# Dash22_LEDS.net
KiCad netlist of a schematic drawn in Altium Designer
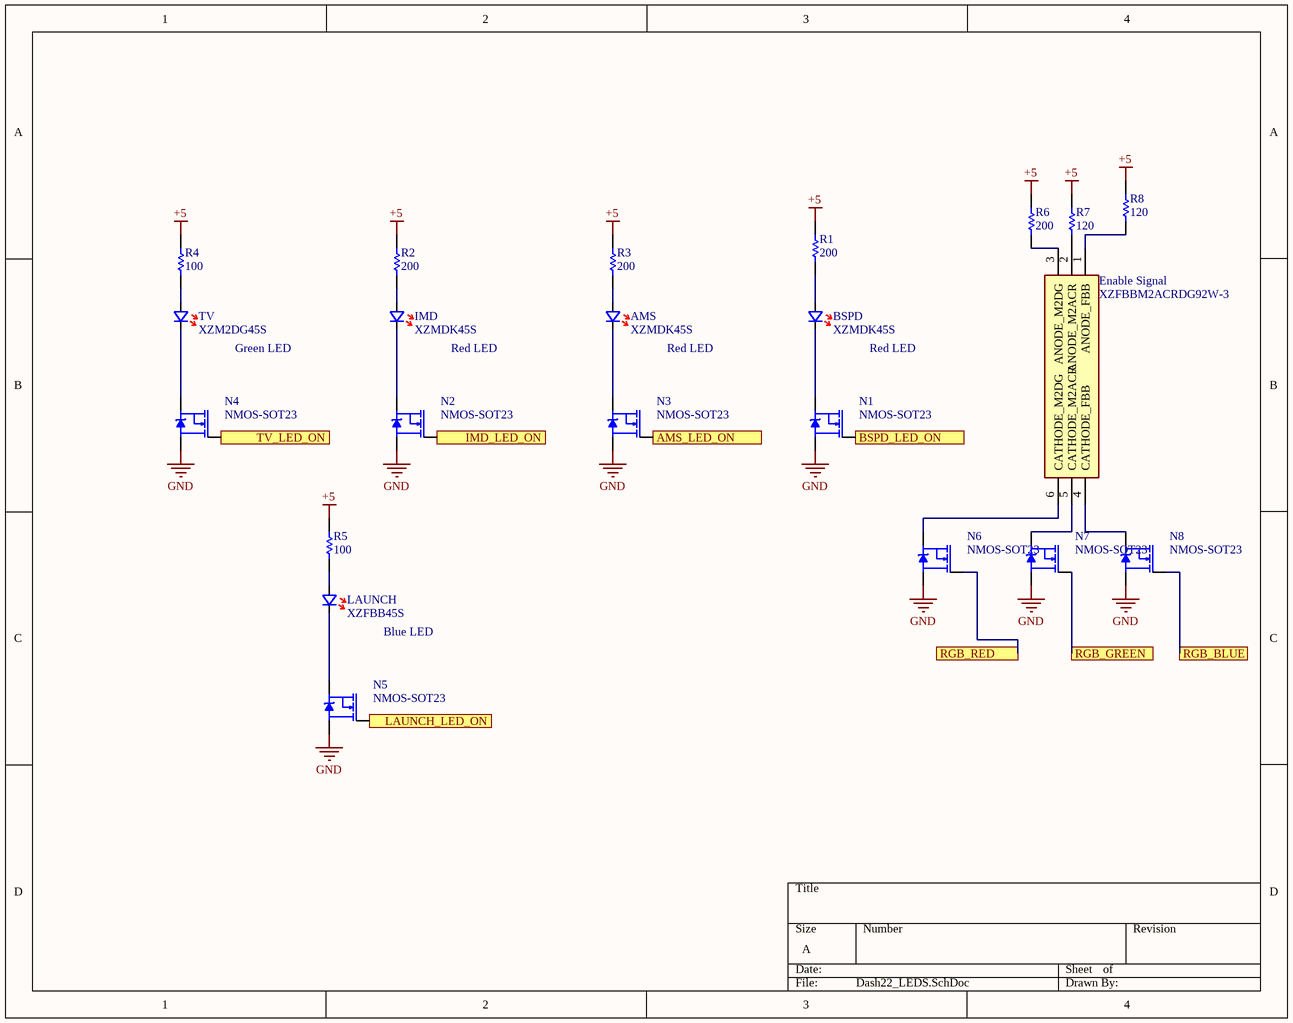
[diagram p0: Dash22_LEDS.SchDoc]

(export (version "E")
  (design (tool "Eeschema 10.0.6"))
  (components
    (comp (ref "AMS")
      (value "XZMDK45S")
      (footprint "LED_XZFBB45S")
      (fields (field (name "SOURCE") "ife19_Elec_Library.schlib"))
      (libsource (lib "") (part "Symbol_1"))
    )
    (comp (ref "BSPD")
      (value "XZMDK45S")
      (footprint "LED_XZFBB45S")
      (fields (field (name "SOURCE") "ife19_Elec_Library.schlib"))
      (libsource (lib "") (part "Symbol_1"))
    )
    (comp (ref "Enable Signal")
      (value "XZFBBM2ACRDG92W-3")
      (footprint "SamacSys:XZFBBM2ACRDG92W3")
      (description "LED")
      (libsource (lib "*") (part "XZFBBM2ACRDG92W-3"))
    )
    (comp (ref "IMD")
      (value "XZMDK45S")
      (footprint "LED_XZFBB45S")
      (fields (field (name "SOURCE") "ife19_Elec_Library.schlib"))
      (libsource (lib "") (part "Symbol_1"))
    )
    (comp (ref "LAUNCH")
      (value "XZFBB45S")
      (footprint "LED_XZFBB45S")
      (fields (field (name "SOURCE") "ife19_Elec_Library.schlib"))
      (libsource (lib "") (part "Symbol_1"))
    )
    (comp (ref "N1")
      (value "NMOS-SOT23")
      (footprint "SOT23")
      (fields (field (name "SOURCE") "ife19_Elec_Library.schlib"))
      (libsource (lib "Illini Formula Electric") (part "NMOS-SOT23"))
    )
    (comp (ref "N2")
      (value "NMOS-SOT23")
      (footprint "SOT23")
      (fields (field (name "SOURCE") "ife19_Elec_Library.schlib"))
      (libsource (lib "Illini Formula Electric") (part "NMOS-SOT23"))
    )
    (comp (ref "N3")
      (value "NMOS-SOT23")
      (footprint "SOT23")
      (fields (field (name "SOURCE") "ife19_Elec_Library.schlib"))
      (libsource (lib "Illini Formula Electric") (part "NMOS-SOT23"))
    )
    (comp (ref "N4")
      (value "NMOS-SOT23")
      (footprint "SOT23")
      (fields (field (name "SOURCE") "ife19_Elec_Library.schlib"))
      (libsource (lib "Illini Formula Electric") (part "NMOS-SOT23"))
    )
    (comp (ref "N5")
      (value "NMOS-SOT23")
      (footprint "SOT23")
      (fields (field (name "SOURCE") "ife19_Elec_Library.schlib"))
      (libsource (lib "Illini Formula Electric") (part "NMOS-SOT23"))
    )
    (comp (ref "N6")
      (value "NMOS-SOT23")
      (footprint "SOT23")
      (fields (field (name "SOURCE") "ife19_Elec_Library.schlib"))
      (libsource (lib "Illini Formula Electric") (part "NMOS-SOT23"))
    )
    (comp (ref "N7")
      (value "NMOS-SOT23")
      (footprint "SOT23")
      (fields (field (name "SOURCE") "ife19_Elec_Library.schlib"))
      (libsource (lib "Illini Formula Electric") (part "NMOS-SOT23"))
    )
    (comp (ref "N8")
      (value "NMOS-SOT23")
      (footprint "SOT23")
      (fields (field (name "SOURCE") "ife19_Elec_Library.schlib"))
      (libsource (lib "Illini Formula Electric") (part "NMOS-SOT23"))
    )
    (comp (ref "R1")
      (value "200")
      (footprint "RESC1608X55X25ML10T15")
      (description "Chip Resistor, 0 Ohm, 0.1 W, -55 to 155 degC, 0603 (1608 Metric)")
      (libsource (lib "Illini Formula Electric") (part "Symbol"))
    )
    (comp (ref "R2")
      (value "200")
      (footprint "RESC1608X55X25ML10T15")
      (description "Chip Resistor, 0 Ohm, 0.1 W, -55 to 155 degC, 0603 (1608 Metric)")
      (libsource (lib "Illini Formula Electric") (part "Symbol"))
    )
    (comp (ref "R3")
      (value "200")
      (footprint "RESC1608X55X25ML10T15")
      (description "Chip Resistor, 0 Ohm, 0.1 W, -55 to 155 degC, 0603 (1608 Metric)")
      (libsource (lib "Illini Formula Electric") (part "Symbol"))
    )
    (comp (ref "R4")
      (value "100")
      (footprint "RESC1608X55X25ML10T15")
      (description "Chip Resistor, 0 Ohm, 0.1 W, -55 to 155 degC, 0603 (1608 Metric)")
      (libsource (lib "Illini Formula Electric") (part "Symbol"))
    )
    (comp (ref "R5")
      (value "100")
      (footprint "RESC1608X55X25ML10T15")
      (description "Chip Resistor, 0 Ohm, 0.1 W, -55 to 155 degC, 0603 (1608 Metric)")
      (libsource (lib "Illini Formula Electric") (part "Symbol"))
    )
    (comp (ref "R6")
      (value "200")
      (footprint "RESC1608X55X25ML10T15")
      (description "Chip Resistor, 0 Ohm, 0.1 W, -55 to 155 degC, 0603 (1608 Metric)")
      (libsource (lib "Illini Formula Electric") (part "Symbol"))
    )
    (comp (ref "R7")
      (value "120")
      (footprint "RESC1608X55X25ML10T15")
      (description "Chip Resistor, 0 Ohm, 0.1 W, -55 to 155 degC, 0603 (1608 Metric)")
      (libsource (lib "Illini Formula Electric") (part "Symbol"))
    )
    (comp (ref "R8")
      (value "120")
      (footprint "RESC1608X55X25ML10T15")
      (description "Chip Resistor, 0 Ohm, 0.1 W, -55 to 155 degC, 0603 (1608 Metric)")
      (libsource (lib "Illini Formula Electric") (part "Symbol"))
    )
    (comp (ref "TV")
      (value "XZM2DG45S")
      (footprint "LED_XZFBB45S")
      (fields (field (name "SOURCE") "ife19_Elec_Library.schlib"))
      (libsource (lib "") (part "Symbol_1"))
    )
  )
  (nets
    (net (code "1") (name "+5") (class "Default")
      (node (ref "R1") (pin "2") (pinfunction "2_2") (pintype "passive"))
      (node (ref "R2") (pin "2") (pinfunction "2_2") (pintype "passive"))
      (node (ref "R3") (pin "2") (pinfunction "2_2") (pintype "passive"))
      (node (ref "R4") (pin "2") (pinfunction "2_2") (pintype "passive"))
      (node (ref "R5") (pin "2") (pinfunction "2_2") (pintype "passive"))
      (node (ref "R6") (pin "2") (pinfunction "2_2") (pintype "passive"))
      (node (ref "R7") (pin "2") (pinfunction "2_2") (pintype "passive"))
      (node (ref "R8") (pin "2") (pinfunction "2_2") (pintype "passive"))
    )
    (net (code "2") (name "/AMS_LED_ON") (class "Default")
      (node (ref "N3") (pin "1") (pinfunction "G_1") (pintype "passive"))
    )
    (net (code "3") (name "/BSPD_LED_ON") (class "Default")
      (node (ref "N1") (pin "1") (pinfunction "G_1") (pintype "passive"))
    )
    (net (code "4") (name "/IMD_LED_ON") (class "Default")
      (node (ref "N2") (pin "1") (pinfunction "G_1") (pintype "passive"))
    )
    (net (code "5") (name "/LAUNCH_LED_ON") (class "Default")
      (node (ref "N5") (pin "1") (pinfunction "G_1") (pintype "passive"))
    )
    (net (code "6") (name "/RGB_BLUE") (class "Default")
      (node (ref "N8") (pin "1") (pinfunction "G_1") (pintype "passive"))
    )
    (net (code "7") (name "/RGB_GREEN") (class "Default")
      (node (ref "N7") (pin "1") (pinfunction "G_1") (pintype "passive"))
    )
    (net (code "8") (name "/RGB_RED") (class "Default")
      (node (ref "N6") (pin "1") (pinfunction "G_1") (pintype "passive"))
    )
    (net (code "9") (name "/TV_LED_ON") (class "Default")
      (node (ref "N4") (pin "1") (pinfunction "G_1") (pintype "passive"))
    )
    (net (code "10") (name "GND") (class "Default")
      (node (ref "N1") (pin "2") (pinfunction "S_2") (pintype "passive"))
      (node (ref "N2") (pin "2") (pinfunction "S_2") (pintype "passive"))
      (node (ref "N3") (pin "2") (pinfunction "S_2") (pintype "passive"))
      (node (ref "N4") (pin "2") (pinfunction "S_2") (pintype "passive"))
      (node (ref "N5") (pin "2") (pinfunction "S_2") (pintype "passive"))
      (node (ref "N6") (pin "2") (pinfunction "S_2") (pintype "passive"))
      (node (ref "N7") (pin "2") (pinfunction "S_2") (pintype "passive"))
      (node (ref "N8") (pin "2") (pinfunction "S_2") (pintype "passive"))
    )
    (net (code "11") (name "Net-(AMS-PadA)") (class "Default")
      (node (ref "AMS") (pin "A") (pinfunction "A_A") (pintype "passive"))
      (node (ref "R3") (pin "1") (pinfunction "1_1") (pintype "passive"))
    )
    (net (code "12") (name "Net-(BSPD-PadA)") (class "Default")
      (node (ref "BSPD") (pin "A") (pinfunction "A_A") (pintype "passive"))
      (node (ref "R1") (pin "1") (pinfunction "1_1") (pintype "passive"))
    )
    (net (code "13") (name "Net-(Enable Signal-ANODE_FBB)") (class "Default")
      (node (ref "Enable Signal") (pin "1") (pinfunction "ANODE_FBB_1") (pintype "passive"))
      (node (ref "R8") (pin "1") (pinfunction "1_1") (pintype "passive"))
    )
    (net (code "14") (name "Net-(Enable Signal-ANODE_M2ACR)") (class "Default")
      (node (ref "Enable Signal") (pin "2") (pinfunction "ANODE_M2ACR_2") (pintype "passive"))
      (node (ref "R7") (pin "1") (pinfunction "1_1") (pintype "passive"))
    )
    (net (code "15") (name "Net-(Enable Signal-ANODE_M2DG)") (class "Default")
      (node (ref "Enable Signal") (pin "3") (pinfunction "ANODE_M2DG_3") (pintype "passive"))
      (node (ref "R6") (pin "1") (pinfunction "1_1") (pintype "passive"))
    )
    (net (code "16") (name "Net-(Enable Signal-CATHODE_FBB)") (class "Default")
      (node (ref "Enable Signal") (pin "4") (pinfunction "CATHODE_FBB_4") (pintype "passive"))
      (node (ref "N8") (pin "3") (pinfunction "D_3") (pintype "passive"))
    )
    (net (code "17") (name "Net-(Enable Signal-CATHODE_M2ACR)") (class "Default")
      (node (ref "Enable Signal") (pin "5") (pinfunction "CATHODE_M2ACR_5") (pintype "passive"))
      (node (ref "N7") (pin "3") (pinfunction "D_3") (pintype "passive"))
    )
    (net (code "18") (name "Net-(Enable Signal-CATHODE_M2DG)") (class "Default")
      (node (ref "Enable Signal") (pin "6") (pinfunction "CATHODE_M2DG_6") (pintype "passive"))
      (node (ref "N6") (pin "3") (pinfunction "D_3") (pintype "passive"))
    )
    (net (code "19") (name "Net-(IMD-PadA)") (class "Default")
      (node (ref "IMD") (pin "A") (pinfunction "A_A") (pintype "passive"))
      (node (ref "R2") (pin "1") (pinfunction "1_1") (pintype "passive"))
    )
    (net (code "20") (name "Net-(LAUNCH-PadA)") (class "Default")
      (node (ref "LAUNCH") (pin "A") (pinfunction "A_A") (pintype "passive"))
      (node (ref "R5") (pin "1") (pinfunction "1_1") (pintype "passive"))
    )
    (net (code "21") (name "Net-(N1-D)") (class "Default")
      (node (ref "BSPD") (pin "K") (pinfunction "K_K") (pintype "passive"))
      (node (ref "N1") (pin "3") (pinfunction "D_3") (pintype "passive"))
    )
    (net (code "22") (name "Net-(N2-D)") (class "Default")
      (node (ref "IMD") (pin "K") (pinfunction "K_K") (pintype "passive"))
      (node (ref "N2") (pin "3") (pinfunction "D_3") (pintype "passive"))
    )
    (net (code "23") (name "Net-(N3-D)") (class "Default")
      (node (ref "AMS") (pin "K") (pinfunction "K_K") (pintype "passive"))
      (node (ref "N3") (pin "3") (pinfunction "D_3") (pintype "passive"))
    )
    (net (code "24") (name "Net-(N4-D)") (class "Default")
      (node (ref "N4") (pin "3") (pinfunction "D_3") (pintype "passive"))
      (node (ref "TV") (pin "K") (pinfunction "K_K") (pintype "passive"))
    )
    (net (code "25") (name "Net-(N5-D)") (class "Default")
      (node (ref "LAUNCH") (pin "K") (pinfunction "K_K") (pintype "passive"))
      (node (ref "N5") (pin "3") (pinfunction "D_3") (pintype "passive"))
    )
    (net (code "26") (name "Net-(R4-Pad1)") (class "Default")
      (node (ref "R4") (pin "1") (pinfunction "1_1") (pintype "passive"))
      (node (ref "TV") (pin "A") (pinfunction "A_A") (pintype "passive"))
    )
  )
)
